# SCH_WSTICKSR.net
KiCad netlist of a schematic drawn in Altium Designer
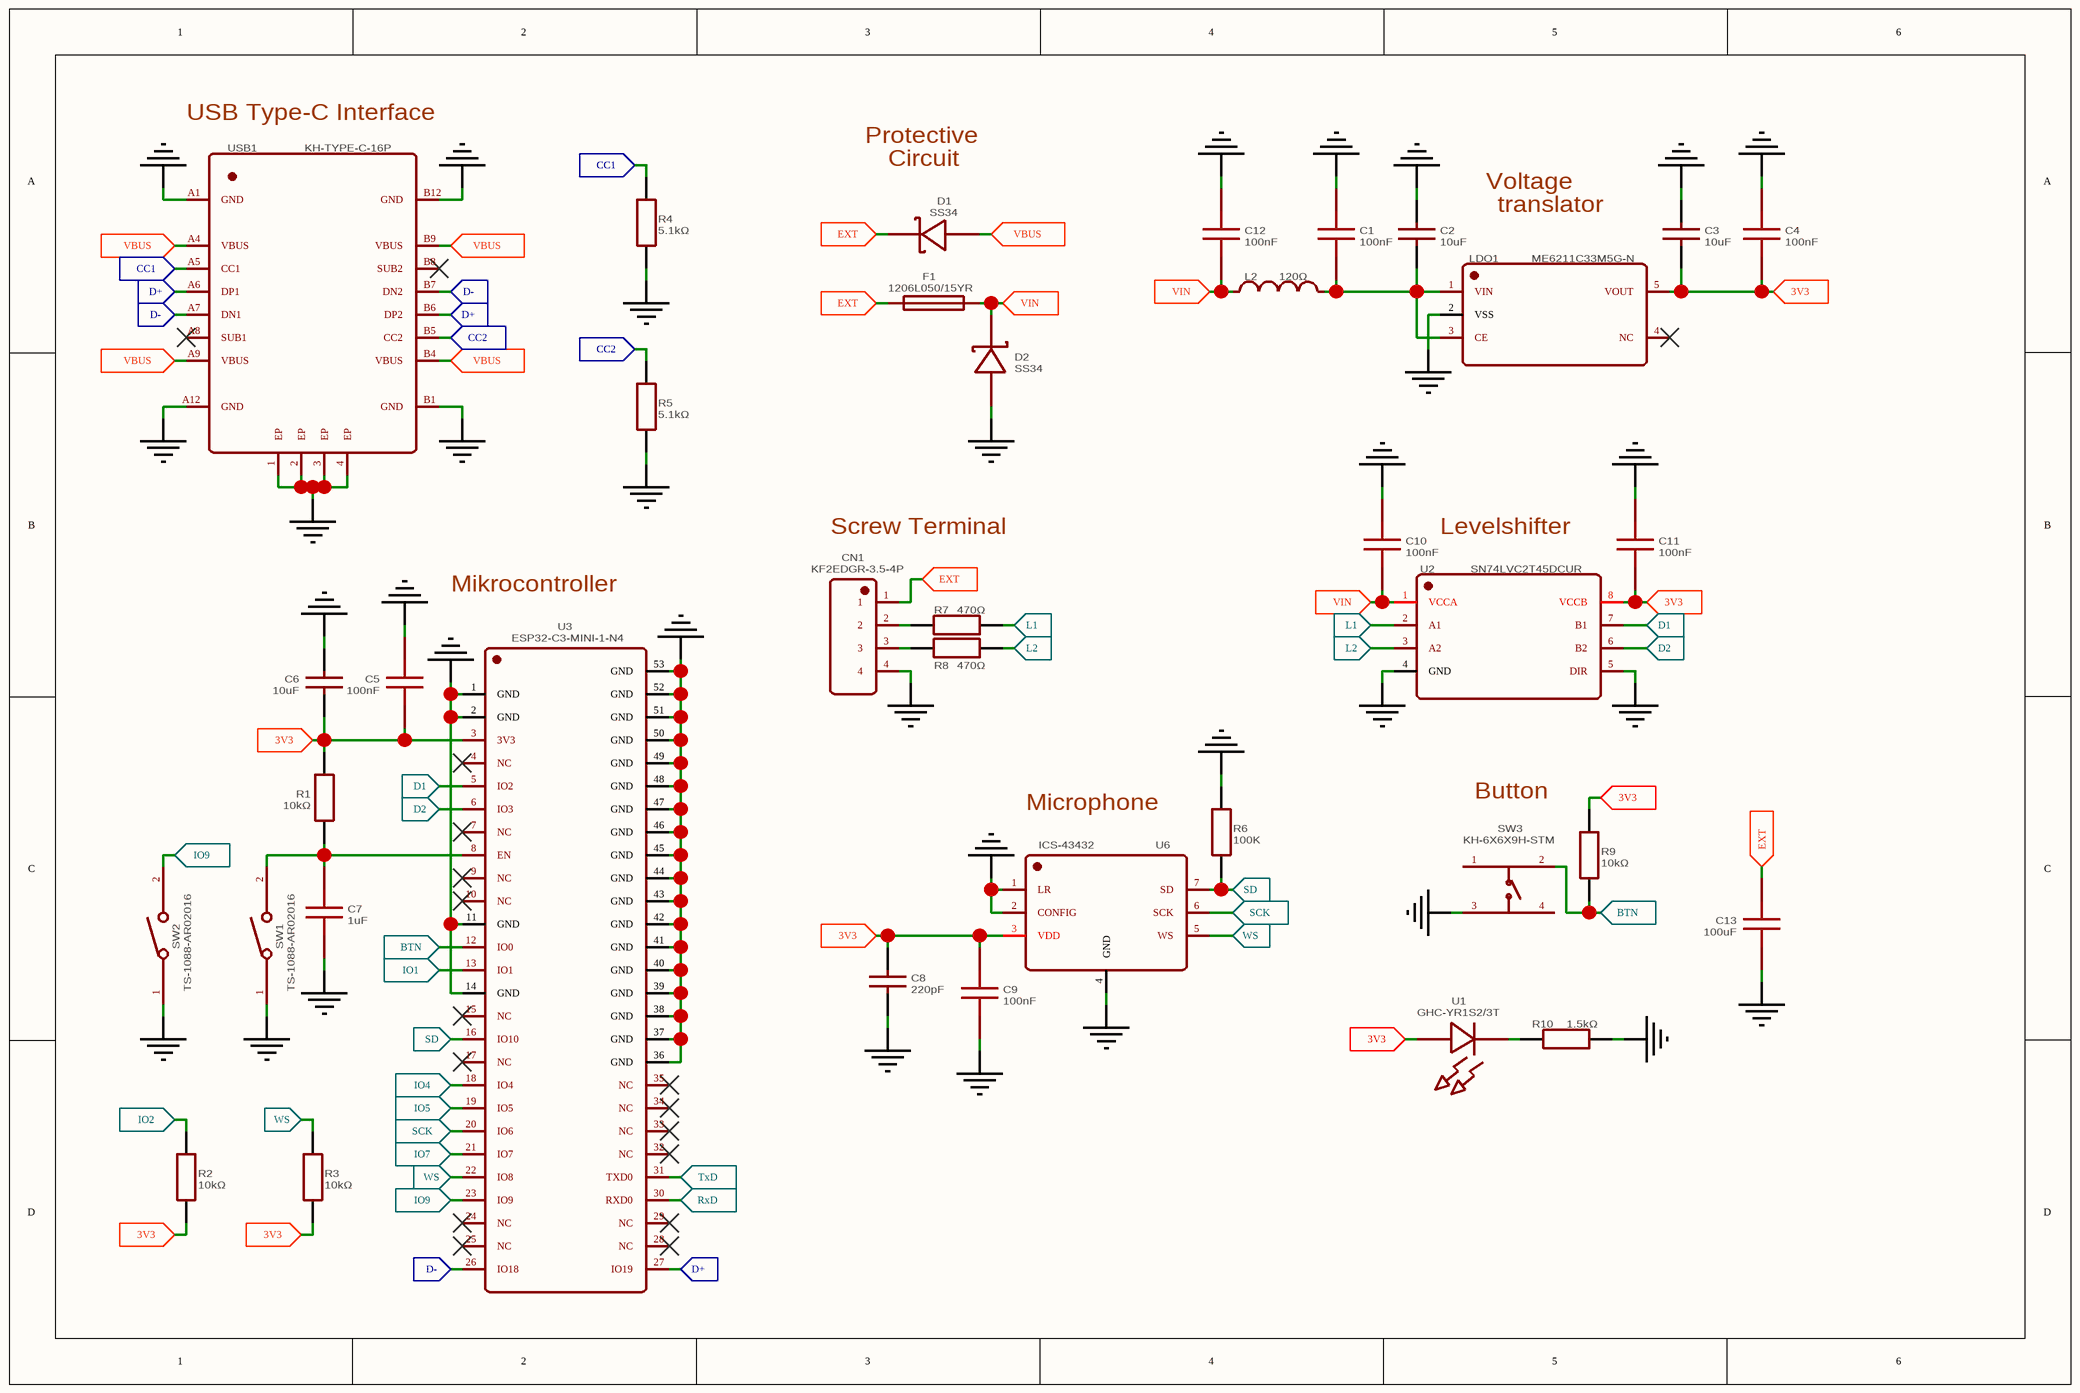
[diagram p0: SCH_WSTICKSR.schdoc]

(export (version "E")
  (design (tool "Eeschema 10.0.6"))
  (components
    (comp (ref "C1")
      (value "100nF")
      (fields
        (field (name "BOM_SUPPLIER PART") "C307331")
        (field (name "BOM_MANUFACTURER PART") "CL05B104KB54PNC")
        (field (name "CONTRIBUTOR") "LCSC")
      )
      (libsource (lib "altium-import") (part "root_3_100nF_"))
    )
    (comp (ref "C2")
      (value "10uF")
      (fields
        (field (name "BOM_MANUFACTURER PART") "CL05A106MQ5NUNC")
        (field (name "BOM_SUPPLIER PART") "C15525")
      )
      (libsource (lib "") (part "root_3_10uF__1"))
    )
    (comp (ref "C3")
      (value "10uF")
      (fields
        (field (name "BOM_MANUFACTURER PART") "CL05A106MQ5NUNC")
        (field (name "BOM_SUPPLIER PART") "C15525")
      )
      (libsource (lib "") (part "root_3_10uF__1"))
    )
    (comp (ref "C4")
      (value "100nF")
      (fields
        (field (name "BOM_SUPPLIER PART") "C307331")
        (field (name "BOM_MANUFACTURER PART") "CL05B104KB54PNC")
        (field (name "CONTRIBUTOR") "LCSC")
      )
      (libsource (lib "altium-import") (part "root_3_100nF_"))
    )
    (comp (ref "C5")
      (value "100nF")
      (fields
        (field (name "BOM_SUPPLIER PART") "C307331")
        (field (name "BOM_MANUFACTURER PART") "CL05B104KB54PNC")
        (field (name "CONTRIBUTOR") "LCSC")
      )
      (libsource (lib "") (part "root_3_100nF__1"))
    )
    (comp (ref "C6")
      (value "10uF")
      (fields
        (field (name "BOM_MANUFACTURER PART") "CL05A106MQ5NUNC")
        (field (name "BOM_SUPPLIER PART") "C15525")
      )
      (libsource (lib "altium-import") (part "root_3_10uF_"))
    )
    (comp (ref "C7")
      (value "1uF")
      (fields
        (field (name "BOM_MANUFACTURER PART") "CL05A105KA5NQNC")
        (field (name "BOM_SUPPLIER PART") "C52923")
      )
      (libsource (lib "altium-import") (part "root_3_1uF_"))
    )
    (comp (ref "C8")
      (value "220pF")
      (fields
        (field (name "BOM_MANUFACTURER PART") "0402B221K500NT")
        (field (name "BOM_SUPPLIER PART") "C1530")
      )
      (libsource (lib "altium-import") (part "root_3_220pF_"))
    )
    (comp (ref "C9")
      (value "100nF")
      (fields
        (field (name "BOM_SUPPLIER PART") "C307331")
        (field (name "BOM_MANUFACTURER PART") "CL05B104KB54PNC")
        (field (name "CONTRIBUTOR") "LCSC")
      )
      (libsource (lib "altium-import") (part "root_3_100nF_"))
    )
    (comp (ref "C10")
      (value "100nF")
      (fields
        (field (name "BOM_SUPPLIER PART") "C307331")
        (field (name "BOM_MANUFACTURER PART") "CL05B104KB54PNC")
        (field (name "CONTRIBUTOR") "LCSC")
      )
      (libsource (lib "altium-import") (part "root_3_100nF_"))
    )
    (comp (ref "C11")
      (value "100nF")
      (fields
        (field (name "BOM_SUPPLIER PART") "C307331")
        (field (name "BOM_MANUFACTURER PART") "CL05B104KB54PNC")
        (field (name "CONTRIBUTOR") "LCSC")
      )
      (libsource (lib "altium-import") (part "root_3_100nF_"))
    )
    (comp (ref "C12")
      (value "100nF")
      (fields
        (field (name "BOM_SUPPLIER PART") "C307331")
        (field (name "BOM_MANUFACTURER PART") "CL05B104KB54PNC")
        (field (name "CONTRIBUTOR") "LCSC")
      )
      (libsource (lib "altium-import") (part "root_3_100nF_"))
    )
    (comp (ref "C13")
      (value "100uF")
      (fields
        (field (name "BOM_SUPPLIER PART") "C394395")
        (field (name "BOM_MANUFACTURER PART") "EMK325ABJ107MM-T")
        (field (name "CONTRIBUTOR") "LCSC")
      )
      (libsource (lib "altium-import") (part "root_0_100uF_"))
    )
    (comp (ref "CN1")
      (value "KF2EDGR-3.5-4P")
      (fields (field (name "BOM_SUPPLIER PART") "C441173") (field (name "CONTRIBUTOR") "LCSC"))
      (libsource (lib "altium-import") (part "root_0_KF2EDGR-3.5-4P_"))
    )
    (comp (ref "D1")
      (value "SS34")
      (fields (field (name "BOM_SUPPLIER PART") "C13762"))
      (libsource (lib "altium-import") (part "root_0_SS34_"))
    )
    (comp (ref "D2")
      (value "SS34")
      (fields (field (name "BOM_SUPPLIER PART") "C13762"))
      (libsource (lib "altium-import") (part "root_3_SS34_"))
    )
    (comp (ref "F1")
      (value "1206L050/15YR")
      (fields (field (name "BOM_SUPPLIER PART") "C151162") (field (name "CONTRIBUTOR") "LCSC"))
      (libsource (lib "altium-import") (part "root_0_1206L050/15YR_"))
    )
    (comp (ref "L2")
      (value "120Ω")
      (fields
        (field (name "BOM_MANUFACTURER PART") "PZ1608D121-2R0TF")
        (field (name "BOM_SUPPLIER PART") "C42102")
      )
      (libsource (lib "altium-import") (part "root_0_120Ω_"))
    )
    (comp (ref "LDO1")
      (value "ME6211C33M5G-N")
      (fields (field (name "BOM_SUPPLIER PART") "C82942"))
      (libsource (lib "altium-import") (part "root_0_ME6211C33M5G-N_"))
    )
    (comp (ref "R1")
      (value "10kΩ")
      (fields
        (field (name "BOM_MANUFACTURER PART") "0402WGF1002TCE")
        (field (name "BOM_SUPPLIER PART") "C25744")
      )
      (libsource (lib "altium-import") (part "root_3_10kΩ_"))
    )
    (comp (ref "R2")
      (value "10kΩ")
      (fields
        (field (name "BOM_MANUFACTURER PART") "0402WGF1002TCE")
        (field (name "BOM_SUPPLIER PART") "C25744")
      )
      (libsource (lib "altium-import") (part "root_3_10kΩ_"))
    )
    (comp (ref "R3")
      (value "10kΩ")
      (fields
        (field (name "BOM_MANUFACTURER PART") "0402WGF1002TCE")
        (field (name "BOM_SUPPLIER PART") "C25744")
      )
      (libsource (lib "altium-import") (part "root_3_10kΩ_"))
    )
    (comp (ref "R4")
      (value "5.1kΩ")
      (fields
        (field (name "BOM_MANUFACTURER PART") "0402WGF5101TCE")
        (field (name "BOM_SUPPLIER PART") "C25905")
      )
      (libsource (lib "altium-import") (part "root_3_5.1kΩ_"))
    )
    (comp (ref "R5")
      (value "5.1kΩ")
      (fields
        (field (name "BOM_MANUFACTURER PART") "0402WGF5101TCE")
        (field (name "BOM_SUPPLIER PART") "C25905")
      )
      (libsource (lib "altium-import") (part "root_3_5.1kΩ_"))
    )
    (comp (ref "R6")
      (value "100K")
      (fields
        (field (name "BOM_MANUFACTURER PART") "0402WGF1003TCE")
        (field (name "BOM_SUPPLIER PART") "C25741")
      )
      (libsource (lib "altium-import") (part "root_3_100K_"))
    )
    (comp (ref "R7")
      (value "470Ω")
      (fields
        (field (name "BOM_MANUFACTURER PART") "0402WGF4700TCE")
        (field (name "BOM_SUPPLIER PART") "C25117")
      )
      (libsource (lib "altium-import") (part "root_0_470Ω_"))
    )
    (comp (ref "R8")
      (value "470Ω")
      (fields
        (field (name "BOM_MANUFACTURER PART") "0402WGF4700TCE")
        (field (name "BOM_SUPPLIER PART") "C25117")
      )
      (libsource (lib "altium-import") (part "root_0_470Ω_"))
    )
    (comp (ref "R9")
      (value "10kΩ")
      (fields
        (field (name "BOM_MANUFACTURER PART") "0402WGF1002TCE")
        (field (name "BOM_SUPPLIER PART") "C25744")
      )
      (libsource (lib "altium-import") (part "root_3_10kΩ_"))
    )
    (comp (ref "R10")
      (value "1.5kΩ")
      (fields
        (field (name "BOM_MANUFACTURER PART") "0402WGF1501TCE")
        (field (name "BOM_SUPPLIER PART") "C25867")
      )
      (libsource (lib "altium-import") (part "root_0_1.5kΩ_"))
    )
    (comp (ref "SW1")
      (value "TS-1088-AR02016")
      (fields (field (name "BOM_SUPPLIER PART") "C720477") (field (name "CONTRIBUTOR") "LCSC"))
      (libsource (lib "altium-import") (part "root_1_TS-1088-AR02016_"))
    )
    (comp (ref "SW2")
      (value "TS-1088-AR02016")
      (fields (field (name "BOM_SUPPLIER PART") "C720477") (field (name "CONTRIBUTOR") "LCSC"))
      (libsource (lib "altium-import") (part "root_1_TS-1088-AR02016_"))
    )
    (comp (ref "SW3")
      (value "KH-6X6X9H-STM")
      (fields (field (name "BOM_SUPPLIER PART") "C2837535") (field (name "CONTRIBUTOR") "LCSC"))
      (libsource (lib "altium-import") (part "root_0_KH-6X6X9H-STM_"))
    )
    (comp (ref "U1")
      (value "GHC-YR1S2/3T")
      (fields
        (field (name "BOM_SUPPLIER PART") "C2973113")
        (field (name "BOM_MANUFACTURER PART") "19-21/GHC-YR1S2/3T")
        (field (name "CONTRIBUTOR") "LCSC")
      )
      (libsource (lib "altium-import") (part "root_2_GHC-YR1S2/3T_"))
    )
    (comp (ref "U2")
      (value "SN74LVC2T45DCUR")
      (fields (field (name "BOM_SUPPLIER PART") "C15741"))
      (libsource (lib "altium-import") (part "root_0_SN74LVC2T45DCUR_"))
    )
    (comp (ref "U3")
      (value "ESP32-C3-MINI-1-N4")
      (fields (field (name "BOM_SUPPLIER PART") "C2838502") (field (name "CONTRIBUTOR") "LCSC"))
      (libsource (lib "altium-import") (part "root_0_ESP32-C3-MINI-1-N4_"))
    )
    (comp (ref "U6")
      (value "ICS-43432")
      (fields (field (name "BOM_SUPPLIER PART") "C574021") (field (name "CONTRIBUTOR") "LCSC"))
      (libsource (lib "altium-import") (part "root_0_ICS-43432_"))
    )
    (comp (ref "USB1")
      (value "KH-TYPE-C-16P")
      (fields (field (name "BOM_SUPPLIER PART") "C709357") (field (name "CONTRIBUTOR") "LCSC"))
      (libsource (lib "altium-import") (part "root_0_KH-TYPE-C-16P_"))
    )
  )
  (nets
    (net (code "1") (name "/3V3") (class "Default")
      (node (ref "C11") (pin "2") (pinfunction "2_2") (pintype "passive"))
      (node (ref "C3") (pin "2") (pinfunction "2_2") (pintype "passive"))
      (node (ref "C4") (pin "2") (pinfunction "2_2") (pintype "passive"))
      (node (ref "C5") (pin "2") (pinfunction "2_2") (pintype "passive"))
      (node (ref "C6") (pin "2") (pinfunction "2_2") (pintype "passive"))
      (node (ref "C8") (pin "1") (pinfunction "1_1") (pintype "passive"))
      (node (ref "C9") (pin "1") (pinfunction "1_1") (pintype "passive"))
      (node (ref "LDO1") (pin "5") (pinfunction "VOUT_5") (pintype "passive"))
      (node (ref "R1") (pin "1") (pinfunction "1_1") (pintype "passive"))
      (node (ref "R2") (pin "2") (pinfunction "2_2") (pintype "passive"))
      (node (ref "R3") (pin "2") (pinfunction "2_2") (pintype "passive"))
      (node (ref "R9") (pin "1") (pinfunction "1_1") (pintype "passive"))
      (node (ref "U1") (pin "1") (pinfunction "+_1") (pintype "passive"))
      (node (ref "U2") (pin "8") (pinfunction "VCCB_8") (pintype "passive"))
      (node (ref "U3") (pin "3") (pinfunction "3V3_3") (pintype "passive"))
      (node (ref "U6") (pin "3") (pinfunction "VDD_3") (pintype "passive"))
    )
    (net (code "2") (name "/BTN") (class "Default")
      (node (ref "R9") (pin "2") (pinfunction "2_2") (pintype "passive"))
      (node (ref "SW3") (pin "2") (pinfunction "B_2") (pintype "passive"))
      (node (ref "U3") (pin "12") (pinfunction "IO0_12") (pintype "passive"))
    )
    (net (code "3") (name "/CC1") (class "Default")
      (node (ref "R4") (pin "1") (pinfunction "1_1") (pintype "passive"))
      (node (ref "USB1") (pin "A5") (pinfunction "CC1_A5") (pintype "passive"))
    )
    (net (code "4") (name "/CC2") (class "Default")
      (node (ref "R5") (pin "1") (pinfunction "1_1") (pintype "passive"))
      (node (ref "USB1") (pin "B5") (pinfunction "CC2_B5") (pintype "passive"))
    )
    (net (code "5") (name "/D+") (class "Default")
      (node (ref "U3") (pin "27") (pinfunction "IO19_27") (pintype "passive"))
      (node (ref "USB1") (pin "A6") (pinfunction "DP1_A6") (pintype "passive"))
      (node (ref "USB1") (pin "B6") (pinfunction "DP2_B6") (pintype "passive"))
    )
    (net (code "6") (name "/D-") (class "Default")
      (node (ref "U3") (pin "26") (pinfunction "IO18_26") (pintype "passive"))
      (node (ref "USB1") (pin "A7") (pinfunction "DN1_A7") (pintype "passive"))
      (node (ref "USB1") (pin "B7") (pinfunction "DN2_B7") (pintype "passive"))
    )
    (net (code "7") (name "/D1") (class "Default")
      (node (ref "U2") (pin "7") (pinfunction "B1_7") (pintype "passive"))
      (node (ref "U3") (pin "5") (pinfunction "IO2_5") (pintype "passive"))
    )
    (net (code "8") (name "/D2") (class "Default")
      (node (ref "U2") (pin "6") (pinfunction "B2_6") (pintype "passive"))
      (node (ref "U3") (pin "6") (pinfunction "IO3_6") (pintype "passive"))
    )
    (net (code "9") (name "/EXT") (class "Default")
      (node (ref "C13") (pin "2") (pinfunction "2_2") (pintype "passive"))
      (node (ref "CN1") (pin "1") (pinfunction "1_1") (pintype "passive"))
      (node (ref "D1") (pin "2") (pinfunction "K_2") (pintype "passive"))
      (node (ref "F1") (pin "1") (pinfunction "1_1") (pintype "passive"))
    )
    (net (code "10") (name "/IO1") (class "Default")
      (node (ref "U3") (pin "13") (pinfunction "IO1_13") (pintype "passive"))
    )
    (net (code "11") (name "/IO2") (class "Default")
      (node (ref "R2") (pin "1") (pinfunction "1_1") (pintype "passive"))
    )
    (net (code "12") (name "/IO4") (class "Default")
      (node (ref "U3") (pin "18") (pinfunction "IO4_18") (pintype "passive"))
    )
    (net (code "13") (name "/IO5") (class "Default")
      (node (ref "U3") (pin "19") (pinfunction "IO5_19") (pintype "passive"))
    )
    (net (code "14") (name "/IO7") (class "Default")
      (node (ref "U3") (pin "21") (pinfunction "IO7_21") (pintype "passive"))
    )
    (net (code "15") (name "/IO9") (class "Default")
      (node (ref "SW2") (pin "2") (pinfunction "2_2") (pintype "passive"))
      (node (ref "U3") (pin "23") (pinfunction "IO9_23") (pintype "passive"))
    )
    (net (code "16") (name "/L1") (class "Default")
      (node (ref "R7") (pin "2") (pinfunction "2_2") (pintype "passive"))
      (node (ref "U2") (pin "2") (pinfunction "A1_2") (pintype "passive"))
    )
    (net (code "17") (name "/L2") (class "Default")
      (node (ref "R8") (pin "2") (pinfunction "2_2") (pintype "passive"))
      (node (ref "U2") (pin "3") (pinfunction "A2_3") (pintype "passive"))
    )
    (net (code "18") (name "/RxD") (class "Default")
      (node (ref "U3") (pin "30") (pinfunction "RXD0_30") (pintype "passive"))
    )
    (net (code "19") (name "/SCK") (class "Default")
      (node (ref "U3") (pin "20") (pinfunction "IO6_20") (pintype "passive"))
      (node (ref "U6") (pin "6") (pinfunction "SCK_6") (pintype "passive"))
    )
    (net (code "20") (name "/SD") (class "Default")
      (node (ref "R6") (pin "2") (pinfunction "2_2") (pintype "passive"))
      (node (ref "U3") (pin "16") (pinfunction "IO10_16") (pintype "passive"))
      (node (ref "U6") (pin "7") (pinfunction "SD_7") (pintype "passive"))
    )
    (net (code "21") (name "/TxD") (class "Default")
      (node (ref "U3") (pin "31") (pinfunction "TXD0_31") (pintype "passive"))
    )
    (net (code "22") (name "/VBUS") (class "Default")
      (node (ref "D1") (pin "1") (pinfunction "A_1") (pintype "passive"))
      (node (ref "USB1") (pin "A4") (pinfunction "VBUS_A4") (pintype "passive"))
      (node (ref "USB1") (pin "A9") (pinfunction "VBUS_A9") (pintype "passive"))
      (node (ref "USB1") (pin "B4") (pinfunction "VBUS_B4") (pintype "passive"))
      (node (ref "USB1") (pin "B9") (pinfunction "VBUS_B9") (pintype "passive"))
    )
    (net (code "23") (name "/VIN") (class "Default")
      (node (ref "C10") (pin "2") (pinfunction "2_2") (pintype "passive"))
      (node (ref "C12") (pin "2") (pinfunction "2_2") (pintype "passive"))
      (node (ref "D2") (pin "2") (pinfunction "K_2") (pintype "passive"))
      (node (ref "F1") (pin "2") (pinfunction "2_2") (pintype "passive"))
      (node (ref "L2") (pin "1") (pinfunction "1_1") (pintype "passive"))
      (node (ref "U2") (pin "1") (pinfunction "VCCA_1") (pintype "passive"))
    )
    (net (code "24") (name "/WS") (class "Default")
      (node (ref "R3") (pin "1") (pinfunction "1_1") (pintype "passive"))
      (node (ref "U3") (pin "22") (pinfunction "IO8_22") (pintype "passive"))
      (node (ref "U6") (pin "5") (pinfunction "WS_5") (pintype "passive"))
    )
    (net (code "25") (name "GND") (class "Default")
      (node (ref "C1") (pin "1") (pinfunction "1_1") (pintype "passive"))
      (node (ref "C10") (pin "1") (pinfunction "1_1") (pintype "passive"))
      (node (ref "C11") (pin "1") (pinfunction "1_1") (pintype "passive"))
      (node (ref "C12") (pin "1") (pinfunction "1_1") (pintype "passive"))
      (node (ref "C13") (pin "1") (pinfunction "1_1") (pintype "passive"))
      (node (ref "C2") (pin "1") (pinfunction "1_1") (pintype "passive"))
      (node (ref "C3") (pin "1") (pinfunction "1_1") (pintype "passive"))
      (node (ref "C4") (pin "1") (pinfunction "1_1") (pintype "passive"))
      (node (ref "C5") (pin "1") (pinfunction "1_1") (pintype "passive"))
      (node (ref "C6") (pin "1") (pinfunction "1_1") (pintype "passive"))
      (node (ref "C7") (pin "2") (pinfunction "2_2") (pintype "passive"))
      (node (ref "C8") (pin "2") (pinfunction "2_2") (pintype "passive"))
      (node (ref "C9") (pin "2") (pinfunction "2_2") (pintype "passive"))
      (node (ref "CN1") (pin "4") (pinfunction "4_4") (pintype "passive"))
      (node (ref "D2") (pin "1") (pinfunction "A_1") (pintype "passive"))
      (node (ref "LDO1") (pin "2") (pinfunction "VSS_2") (pintype "passive"))
      (node (ref "R10") (pin "2") (pinfunction "2_2") (pintype "passive"))
      (node (ref "R4") (pin "2") (pinfunction "2_2") (pintype "passive"))
      (node (ref "R5") (pin "2") (pinfunction "2_2") (pintype "passive"))
      (node (ref "R6") (pin "1") (pinfunction "1_1") (pintype "passive"))
      (node (ref "SW1") (pin "1") (pinfunction "1_1") (pintype "passive"))
      (node (ref "SW2") (pin "1") (pinfunction "1_1") (pintype "passive"))
      (node (ref "SW3") (pin "3") (pinfunction "C_3") (pintype "passive"))
      (node (ref "U2") (pin "4") (pinfunction "GND_4") (pintype "passive"))
      (node (ref "U2") (pin "5") (pinfunction "DIR_5") (pintype "passive"))
      (node (ref "U3") (pin "1") (pinfunction "GND_1") (pintype "passive"))
      (node (ref "U3") (pin "11") (pinfunction "GND_11") (pintype "passive"))
      (node (ref "U3") (pin "14") (pinfunction "GND_14") (pintype "passive"))
      (node (ref "U3") (pin "2") (pinfunction "GND_2") (pintype "passive"))
      (node (ref "U3") (pin "36") (pinfunction "GND_36") (pintype "passive"))
      (node (ref "U3") (pin "37") (pinfunction "GND_37") (pintype "passive"))
      (node (ref "U3") (pin "38") (pinfunction "GND_38") (pintype "passive"))
      (node (ref "U3") (pin "39") (pinfunction "GND_39") (pintype "passive"))
      (node (ref "U3") (pin "40") (pinfunction "GND_40") (pintype "passive"))
      (node (ref "U3") (pin "41") (pinfunction "GND_41") (pintype "passive"))
      (node (ref "U3") (pin "42") (pinfunction "GND_42") (pintype "passive"))
      (node (ref "U3") (pin "43") (pinfunction "GND_43") (pintype "passive"))
      (node (ref "U3") (pin "44") (pinfunction "GND_44") (pintype "passive"))
      (node (ref "U3") (pin "45") (pinfunction "GND_45") (pintype "passive"))
      (node (ref "U3") (pin "46") (pinfunction "GND_46") (pintype "passive"))
      (node (ref "U3") (pin "47") (pinfunction "GND_47") (pintype "passive"))
      (node (ref "U3") (pin "48") (pinfunction "GND_48") (pintype "passive"))
      (node (ref "U3") (pin "49") (pinfunction "GND_49") (pintype "passive"))
      (node (ref "U3") (pin "50") (pinfunction "GND_50") (pintype "passive"))
      (node (ref "U3") (pin "51") (pinfunction "GND_51") (pintype "passive"))
      (node (ref "U3") (pin "52") (pinfunction "GND_52") (pintype "passive"))
      (node (ref "U3") (pin "53") (pinfunction "GND_53") (pintype "passive"))
      (node (ref "U6") (pin "1") (pinfunction "LR_1") (pintype "passive"))
      (node (ref "U6") (pin "2") (pinfunction "CONFIG_2") (pintype "passive"))
      (node (ref "U6") (pin "4") (pinfunction "GND_4") (pintype "passive"))
      (node (ref "USB1") (pin "1") (pinfunction "EP_1") (pintype "passive"))
      (node (ref "USB1") (pin "2") (pinfunction "EP_2") (pintype "passive"))
      (node (ref "USB1") (pin "3") (pinfunction "EP_3") (pintype "passive"))
      (node (ref "USB1") (pin "4") (pinfunction "EP_4") (pintype "passive"))
      (node (ref "USB1") (pin "A1") (pinfunction "GND_A1") (pintype "passive"))
      (node (ref "USB1") (pin "A12") (pinfunction "GND_A12") (pintype "passive"))
      (node (ref "USB1") (pin "B1") (pinfunction "GND_B1") (pintype "passive"))
      (node (ref "USB1") (pin "B12") (pinfunction "GND_B12") (pintype "passive"))
    )
    (net (code "26") (name "Net-(CN1-Pad2)") (class "Default")
      (node (ref "CN1") (pin "2") (pinfunction "2_2") (pintype "passive"))
      (node (ref "R7") (pin "1") (pinfunction "1_1") (pintype "passive"))
    )
    (net (code "27") (name "Net-(CN1-Pad3)") (class "Default")
      (node (ref "CN1") (pin "3") (pinfunction "3_3") (pintype "passive"))
      (node (ref "R8") (pin "1") (pinfunction "1_1") (pintype "passive"))
    )
    (net (code "28") (name "Net-(LDO1-CE)") (class "Default")
      (node (ref "C1") (pin "2") (pinfunction "2_2") (pintype "passive"))
      (node (ref "C2") (pin "2") (pinfunction "2_2") (pintype "passive"))
      (node (ref "L2") (pin "2") (pinfunction "2_2") (pintype "passive"))
      (node (ref "LDO1") (pin "1") (pinfunction "VIN_1") (pintype "passive"))
      (node (ref "LDO1") (pin "3") (pinfunction "CE_3") (pintype "passive"))
    )
    (net (code "29") (name "Net-(U1--)") (class "Default")
      (node (ref "R10") (pin "1") (pinfunction "1_1") (pintype "passive"))
      (node (ref "U1") (pin "2") (pinfunction "-_2") (pintype "passive"))
    )
    (net (code "30") (name "Net-(U3-EN)") (class "Default")
      (node (ref "C7") (pin "1") (pinfunction "1_1") (pintype "passive"))
      (node (ref "R1") (pin "2") (pinfunction "2_2") (pintype "passive"))
      (node (ref "SW1") (pin "2") (pinfunction "2_2") (pintype "passive"))
      (node (ref "U3") (pin "8") (pinfunction "EN_8") (pintype "passive"))
    )
    (net (code "31") (name "unconnected-(LDO1-NC-Pad4)") (class "Default")
      (node (ref "LDO1") (pin "4") (pinfunction "NC_4") (pintype "passive+no_connect"))
    )
    (net (code "32") (name "unconnected-(SW3-A-Pad1)") (class "Default")
      (node (ref "SW3") (pin "1") (pinfunction "A_1") (pintype "passive"))
    )
    (net (code "33") (name "unconnected-(SW3-D-Pad4)") (class "Default")
      (node (ref "SW3") (pin "4") (pinfunction "D_4") (pintype "passive"))
    )
    (net (code "34") (name "unconnected-(U3-NC-Pad4)") (class "Default")
      (node (ref "U3") (pin "4") (pinfunction "NC_4") (pintype "passive+no_connect"))
    )
    (net (code "35") (name "unconnected-(U3-NC-Pad7)") (class "Default")
      (node (ref "U3") (pin "7") (pinfunction "NC_7") (pintype "passive+no_connect"))
    )
    (net (code "36") (name "unconnected-(U3-NC-Pad9)") (class "Default")
      (node (ref "U3") (pin "9") (pinfunction "NC_9") (pintype "passive+no_connect"))
    )
    (net (code "37") (name "unconnected-(U3-NC-Pad10)") (class "Default")
      (node (ref "U3") (pin "10") (pinfunction "NC_10") (pintype "passive+no_connect"))
    )
    (net (code "38") (name "unconnected-(U3-NC-Pad15)") (class "Default")
      (node (ref "U3") (pin "15") (pinfunction "NC_15") (pintype "passive+no_connect"))
    )
    (net (code "39") (name "unconnected-(U3-NC-Pad17)") (class "Default")
      (node (ref "U3") (pin "17") (pinfunction "NC_17") (pintype "passive+no_connect"))
    )
    (net (code "40") (name "unconnected-(U3-NC-Pad24)") (class "Default")
      (node (ref "U3") (pin "24") (pinfunction "NC_24") (pintype "passive+no_connect"))
    )
    (net (code "41") (name "unconnected-(U3-NC-Pad25)") (class "Default")
      (node (ref "U3") (pin "25") (pinfunction "NC_25") (pintype "passive+no_connect"))
    )
    (net (code "42") (name "unconnected-(U3-NC-Pad28)") (class "Default")
      (node (ref "U3") (pin "28") (pinfunction "NC_28") (pintype "passive+no_connect"))
    )
    (net (code "43") (name "unconnected-(U3-NC-Pad29)") (class "Default")
      (node (ref "U3") (pin "29") (pinfunction "NC_29") (pintype "passive+no_connect"))
    )
    (net (code "44") (name "unconnected-(U3-NC-Pad32)") (class "Default")
      (node (ref "U3") (pin "32") (pinfunction "NC_32") (pintype "passive+no_connect"))
    )
    (net (code "45") (name "unconnected-(U3-NC-Pad33)") (class "Default")
      (node (ref "U3") (pin "33") (pinfunction "NC_33") (pintype "passive+no_connect"))
    )
    (net (code "46") (name "unconnected-(U3-NC-Pad34)") (class "Default")
      (node (ref "U3") (pin "34") (pinfunction "NC_34") (pintype "passive+no_connect"))
    )
    (net (code "47") (name "unconnected-(U3-NC-Pad35)") (class "Default")
      (node (ref "U3") (pin "35") (pinfunction "NC_35") (pintype "passive+no_connect"))
    )
    (net (code "48") (name "unconnected-(USB1-SUB1-PadA8)") (class "Default")
      (node (ref "USB1") (pin "A8") (pinfunction "SUB1_A8") (pintype "passive+no_connect"))
    )
    (net (code "49") (name "unconnected-(USB1-SUB2-PadB8)") (class "Default")
      (node (ref "USB1") (pin "B8") (pinfunction "SUB2_B8") (pintype "passive+no_connect"))
    )
  )
)
